# SDRAM.net
KiCad netlist of a schematic drawn in Altium Designer
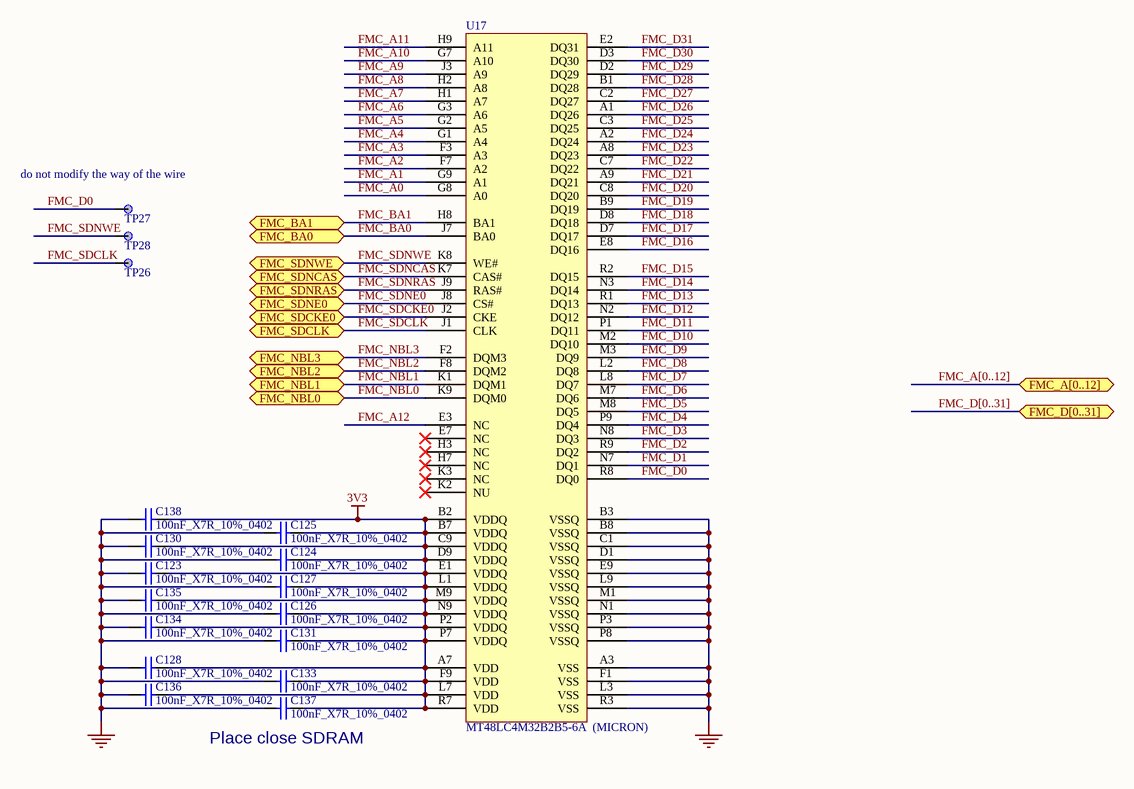
[diagram p0: SDRAM.SchDoc]

(export (version "E")
  (design (tool "Eeschema 10.0.6"))
  (components
    (comp (ref "C123")
      (value "100nF_X7R_10%_0402")
      (footprint "0402C")
      (description "Capacitor,100nF,16V,X7R,10%,0402,YAGEO")
      (libsource (lib "MCD_TOOLS") (part "Cap_100nF_X7R_10%_0402"))
    )
    (comp (ref "C124")
      (value "100nF_X7R_10%_0402")
      (footprint "0402C")
      (description "Capacitor,100nF,16V,X7R,10%,0402,YAGEO")
      (libsource (lib "MCD_TOOLS") (part "Cap_100nF_X7R_10%_0402"))
    )
    (comp (ref "C125")
      (value "100nF_X7R_10%_0402")
      (footprint "0402C")
      (description "Capacitor,100nF,16V,X7R,10%,0402,YAGEO")
      (libsource (lib "MCD_TOOLS") (part "Cap_100nF_X7R_10%_0402"))
    )
    (comp (ref "C126")
      (value "100nF_X7R_10%_0402")
      (footprint "0402C")
      (description "Capacitor,100nF,16V,X7R,10%,0402,YAGEO")
      (libsource (lib "MCD_TOOLS") (part "Cap_100nF_X7R_10%_0402"))
    )
    (comp (ref "C127")
      (value "100nF_X7R_10%_0402")
      (footprint "0402C")
      (description "Capacitor,100nF,16V,X7R,10%,0402,YAGEO")
      (libsource (lib "MCD_TOOLS") (part "Cap_100nF_X7R_10%_0402"))
    )
    (comp (ref "C128")
      (value "100nF_X7R_10%_0402")
      (footprint "0402C")
      (description "Capacitor,100nF,16V,X7R,10%,0402,YAGEO")
      (libsource (lib "MCD_TOOLS") (part "Cap_100nF_X7R_10%_0402"))
    )
    (comp (ref "C130")
      (value "100nF_X7R_10%_0402")
      (footprint "0402C")
      (description "Capacitor,100nF,16V,X7R,10%,0402,YAGEO")
      (libsource (lib "MCD_TOOLS") (part "Cap_100nF_X7R_10%_0402"))
    )
    (comp (ref "C131")
      (value "100nF_X7R_10%_0402")
      (footprint "0402C")
      (description "Capacitor,100nF,16V,X7R,10%,0402,YAGEO")
      (libsource (lib "MCD_TOOLS") (part "Cap_100nF_X7R_10%_0402"))
    )
    (comp (ref "C133")
      (value "100nF_X7R_10%_0402")
      (footprint "0402C")
      (description "Capacitor,100nF,16V,X7R,10%,0402,YAGEO")
      (libsource (lib "MCD_TOOLS") (part "Cap_100nF_X7R_10%_0402"))
    )
    (comp (ref "C134")
      (value "100nF_X7R_10%_0402")
      (footprint "0402C")
      (description "Capacitor,100nF,16V,X7R,10%,0402,YAGEO")
      (libsource (lib "MCD_TOOLS") (part "Cap_100nF_X7R_10%_0402"))
    )
    (comp (ref "C135")
      (value "100nF_X7R_10%_0402")
      (footprint "0402C")
      (description "Capacitor,100nF,16V,X7R,10%,0402,YAGEO")
      (libsource (lib "MCD_TOOLS") (part "Cap_100nF_X7R_10%_0402"))
    )
    (comp (ref "C136")
      (value "100nF_X7R_10%_0402")
      (footprint "0402C")
      (description "Capacitor,100nF,16V,X7R,10%,0402,YAGEO")
      (libsource (lib "MCD_TOOLS") (part "Cap_100nF_X7R_10%_0402"))
    )
    (comp (ref "C137")
      (value "100nF_X7R_10%_0402")
      (footprint "0402C")
      (description "Capacitor,100nF,16V,X7R,10%,0402,YAGEO")
      (libsource (lib "MCD_TOOLS") (part "Cap_100nF_X7R_10%_0402"))
    )
    (comp (ref "C138")
      (value "100nF_X7R_10%_0402")
      (footprint "0402C")
      (description "Capacitor,100nF,16V,X7R,10%,0402,YAGEO")
      (libsource (lib "MCD_TOOLS") (part "Cap_100nF_X7R_10%_0402"))
    )
    (comp (ref "TP26")
      (value "TP")
      (footprint "TP_C40")
      (description "Test Point CMS")
      (libsource (lib "MCD_TOOLS_CONNECTOR") (part "TP"))
    )
    (comp (ref "TP27")
      (value "TP")
      (footprint "TP_C40")
      (description "Test Point CMS")
      (libsource (lib "MCD_TOOLS_CONNECTOR") (part "TP"))
    )
    (comp (ref "TP28")
      (value "TP")
      (footprint "TP_C40")
      (description "Test Point CMS")
      (libsource (lib "MCD_TOOLS_CONNECTOR") (part "TP"))
    )
    (comp (ref "U17")
      (value "MT48LC4M32B2B5-6A  (MICRON)")
      (footprint "FBGA90_0R8_8X13")
      (description "SDRAM 128MBIT (4M x 32) 166MHZ 90-VFBGA (8x13)")
      (libsource (lib "MCD_TOOLS") (part "MT48LC4M32B2B5-6A"))
    )
  )
  (nets
    (net (code "1") (name "/FMC_A0") (class "Default")
      (node (ref "U17") (pin "G8") (pinfunction "A0_G8") (pintype "passive"))
    )
    (net (code "2") (name "/FMC_A1") (class "Default")
      (node (ref "U17") (pin "G9") (pinfunction "A1_G9") (pintype "passive"))
    )
    (net (code "3") (name "/FMC_A2") (class "Default")
      (node (ref "U17") (pin "F7") (pinfunction "A2_F7") (pintype "passive"))
    )
    (net (code "4") (name "/FMC_A3") (class "Default")
      (node (ref "U17") (pin "F3") (pinfunction "A3_F3") (pintype "passive"))
    )
    (net (code "5") (name "/FMC_A4") (class "Default")
      (node (ref "U17") (pin "G1") (pinfunction "A4_G1") (pintype "passive"))
    )
    (net (code "6") (name "/FMC_A5") (class "Default")
      (node (ref "U17") (pin "G2") (pinfunction "A5_G2") (pintype "passive"))
    )
    (net (code "7") (name "/FMC_A6") (class "Default")
      (node (ref "U17") (pin "G3") (pinfunction "A6_G3") (pintype "passive"))
    )
    (net (code "8") (name "/FMC_A7") (class "Default")
      (node (ref "U17") (pin "H1") (pinfunction "A7_H1") (pintype "passive"))
    )
    (net (code "9") (name "/FMC_A8") (class "Default")
      (node (ref "U17") (pin "H2") (pinfunction "A8_H2") (pintype "passive"))
    )
    (net (code "10") (name "/FMC_A9") (class "Default")
      (node (ref "U17") (pin "J3") (pinfunction "A9_J3") (pintype "passive"))
    )
    (net (code "11") (name "/FMC_A10") (class "Default")
      (node (ref "U17") (pin "G7") (pinfunction "A10_G7") (pintype "passive"))
    )
    (net (code "12") (name "/FMC_A11") (class "Default")
      (node (ref "U17") (pin "H9") (pinfunction "A11_H9") (pintype "passive"))
    )
    (net (code "13") (name "/FMC_A12") (class "Default")
      (node (ref "U17") (pin "E3") (pinfunction "NC_E3") (pintype "passive"))
    )
    (net (code "15") (name "/FMC_BA0") (class "Default")
      (node (ref "U17") (pin "J7") (pinfunction "BA0_J7") (pintype "passive"))
    )
    (net (code "16") (name "/FMC_BA1") (class "Default")
      (node (ref "U17") (pin "H8") (pinfunction "BA1_H8") (pintype "passive"))
    )
    (net (code "17") (name "/FMC_D0") (class "Default")
      (node (ref "TP27") (pin "1") (pinfunction "1_1") (pintype "passive"))
      (node (ref "U17") (pin "R8") (pinfunction "DQ0_R8") (pintype "passive"))
    )
    (net (code "18") (name "/FMC_D1") (class "Default")
      (node (ref "U17") (pin "N7") (pinfunction "DQ1_N7") (pintype "passive"))
    )
    (net (code "19") (name "/FMC_D2") (class "Default")
      (node (ref "U17") (pin "R9") (pinfunction "DQ2_R9") (pintype "passive"))
    )
    (net (code "20") (name "/FMC_D3") (class "Default")
      (node (ref "U17") (pin "N8") (pinfunction "DQ3_N8") (pintype "passive"))
    )
    (net (code "21") (name "/FMC_D4") (class "Default")
      (node (ref "U17") (pin "P9") (pinfunction "DQ4_P9") (pintype "passive"))
    )
    (net (code "22") (name "/FMC_D5") (class "Default")
      (node (ref "U17") (pin "M8") (pinfunction "DQ5_M8") (pintype "passive"))
    )
    (net (code "23") (name "/FMC_D6") (class "Default")
      (node (ref "U17") (pin "M7") (pinfunction "DQ6_M7") (pintype "passive"))
    )
    (net (code "24") (name "/FMC_D7") (class "Default")
      (node (ref "U17") (pin "L8") (pinfunction "DQ7_L8") (pintype "passive"))
    )
    (net (code "25") (name "/FMC_D8") (class "Default")
      (node (ref "U17") (pin "L2") (pinfunction "DQ8_L2") (pintype "passive"))
    )
    (net (code "26") (name "/FMC_D9") (class "Default")
      (node (ref "U17") (pin "M3") (pinfunction "DQ9_M3") (pintype "passive"))
    )
    (net (code "27") (name "/FMC_D10") (class "Default")
      (node (ref "U17") (pin "M2") (pinfunction "DQ10_M2") (pintype "passive"))
    )
    (net (code "28") (name "/FMC_D11") (class "Default")
      (node (ref "U17") (pin "P1") (pinfunction "DQ11_P1") (pintype "passive"))
    )
    (net (code "29") (name "/FMC_D12") (class "Default")
      (node (ref "U17") (pin "N2") (pinfunction "DQ12_N2") (pintype "passive"))
    )
    (net (code "30") (name "/FMC_D13") (class "Default")
      (node (ref "U17") (pin "R1") (pinfunction "DQ13_R1") (pintype "passive"))
    )
    (net (code "31") (name "/FMC_D14") (class "Default")
      (node (ref "U17") (pin "N3") (pinfunction "DQ14_N3") (pintype "passive"))
    )
    (net (code "32") (name "/FMC_D15") (class "Default")
      (node (ref "U17") (pin "R2") (pinfunction "DQ15_R2") (pintype "passive"))
    )
    (net (code "33") (name "/FMC_D16") (class "Default")
      (node (ref "U17") (pin "E8") (pinfunction "DQ16_E8") (pintype "passive"))
    )
    (net (code "34") (name "/FMC_D17") (class "Default")
      (node (ref "U17") (pin "D7") (pinfunction "DQ17_D7") (pintype "passive"))
    )
    (net (code "35") (name "/FMC_D18") (class "Default")
      (node (ref "U17") (pin "D8") (pinfunction "DQ18_D8") (pintype "passive"))
    )
    (net (code "36") (name "/FMC_D19") (class "Default")
      (node (ref "U17") (pin "B9") (pinfunction "DQ19_B9") (pintype "passive"))
    )
    (net (code "37") (name "/FMC_D20") (class "Default")
      (node (ref "U17") (pin "C8") (pinfunction "DQ20_C8") (pintype "passive"))
    )
    (net (code "38") (name "/FMC_D21") (class "Default")
      (node (ref "U17") (pin "A9") (pinfunction "DQ21_A9") (pintype "passive"))
    )
    (net (code "39") (name "/FMC_D22") (class "Default")
      (node (ref "U17") (pin "C7") (pinfunction "DQ22_C7") (pintype "passive"))
    )
    (net (code "40") (name "/FMC_D23") (class "Default")
      (node (ref "U17") (pin "A8") (pinfunction "DQ23_A8") (pintype "passive"))
    )
    (net (code "41") (name "/FMC_D24") (class "Default")
      (node (ref "U17") (pin "A2") (pinfunction "DQ24_A2") (pintype "passive"))
    )
    (net (code "42") (name "/FMC_D25") (class "Default")
      (node (ref "U17") (pin "C3") (pinfunction "DQ25_C3") (pintype "passive"))
    )
    (net (code "43") (name "/FMC_D26") (class "Default")
      (node (ref "U17") (pin "A1") (pinfunction "DQ26_A1") (pintype "passive"))
    )
    (net (code "44") (name "/FMC_D27") (class "Default")
      (node (ref "U17") (pin "C2") (pinfunction "DQ27_C2") (pintype "passive"))
    )
    (net (code "45") (name "/FMC_D28") (class "Default")
      (node (ref "U17") (pin "B1") (pinfunction "DQ28_B1") (pintype "passive"))
    )
    (net (code "46") (name "/FMC_D29") (class "Default")
      (node (ref "U17") (pin "D2") (pinfunction "DQ29_D2") (pintype "passive"))
    )
    (net (code "47") (name "/FMC_D30") (class "Default")
      (node (ref "U17") (pin "D3") (pinfunction "DQ30_D3") (pintype "passive"))
    )
    (net (code "48") (name "/FMC_D31") (class "Default")
      (node (ref "U17") (pin "E2") (pinfunction "DQ31_E2") (pintype "passive"))
    )
    (net (code "50") (name "/FMC_NBL0") (class "Default")
      (node (ref "U17") (pin "K9") (pinfunction "DQM0_K9") (pintype "passive"))
    )
    (net (code "51") (name "/FMC_NBL1") (class "Default")
      (node (ref "U17") (pin "K1") (pinfunction "DQM1_K1") (pintype "passive"))
    )
    (net (code "52") (name "/FMC_NBL2") (class "Default")
      (node (ref "U17") (pin "F8") (pinfunction "DQM2_F8") (pintype "passive"))
    )
    (net (code "53") (name "/FMC_NBL3") (class "Default")
      (node (ref "U17") (pin "F2") (pinfunction "DQM3_F2") (pintype "passive"))
    )
    (net (code "54") (name "/FMC_SDCKE0") (class "Default")
      (node (ref "U17") (pin "J2") (pinfunction "CKE_J2") (pintype "passive"))
    )
    (net (code "55") (name "/FMC_SDCLK") (class "Default")
      (node (ref "TP26") (pin "1") (pinfunction "1_1") (pintype "passive"))
      (node (ref "U17") (pin "J1") (pinfunction "CLK_J1") (pintype "passive"))
    )
    (net (code "56") (name "/FMC_SDNCAS") (class "Default")
      (node (ref "U17") (pin "K7") (pinfunction "CAS#_K7") (pintype "passive"))
    )
    (net (code "57") (name "/FMC_SDNE0") (class "Default")
      (node (ref "U17") (pin "J8") (pinfunction "CS#_J8") (pintype "passive"))
    )
    (net (code "58") (name "/FMC_SDNRAS") (class "Default")
      (node (ref "U17") (pin "J9") (pinfunction "RAS#_J9") (pintype "passive"))
    )
    (net (code "59") (name "/FMC_SDNWE") (class "Default")
      (node (ref "TP28") (pin "1") (pinfunction "1_1") (pintype "passive"))
      (node (ref "U17") (pin "K8") (pinfunction "WE#_K8") (pintype "passive"))
    )
    (net (code "60") (name "3V3") (class "Default")
      (node (ref "C123") (pin "2") (pinfunction "2_2") (pintype "passive"))
      (node (ref "C124") (pin "2") (pinfunction "2_2") (pintype "passive"))
      (node (ref "C125") (pin "2") (pinfunction "2_2") (pintype "passive"))
      (node (ref "C126") (pin "2") (pinfunction "2_2") (pintype "passive"))
      (node (ref "C127") (pin "2") (pinfunction "2_2") (pintype "passive"))
      (node (ref "C128") (pin "2") (pinfunction "2_2") (pintype "passive"))
      (node (ref "C130") (pin "2") (pinfunction "2_2") (pintype "passive"))
      (node (ref "C131") (pin "2") (pinfunction "2_2") (pintype "passive"))
      (node (ref "C133") (pin "2") (pinfunction "2_2") (pintype "passive"))
      (node (ref "C134") (pin "2") (pinfunction "2_2") (pintype "passive"))
      (node (ref "C135") (pin "2") (pinfunction "2_2") (pintype "passive"))
      (node (ref "C136") (pin "2") (pinfunction "2_2") (pintype "passive"))
      (node (ref "C137") (pin "2") (pinfunction "2_2") (pintype "passive"))
      (node (ref "C138") (pin "2") (pinfunction "2_2") (pintype "passive"))
      (node (ref "U17") (pin "A7") (pinfunction "VDD_A7") (pintype "passive"))
      (node (ref "U17") (pin "B2") (pinfunction "VDDQ_B2") (pintype "passive"))
      (node (ref "U17") (pin "B7") (pinfunction "VDDQ_B7") (pintype "passive"))
      (node (ref "U17") (pin "C9") (pinfunction "VDDQ_C9") (pintype "passive"))
      (node (ref "U17") (pin "D9") (pinfunction "VDDQ_D9") (pintype "passive"))
      (node (ref "U17") (pin "E1") (pinfunction "VDDQ_E1") (pintype "passive"))
      (node (ref "U17") (pin "F9") (pinfunction "VDD_F9") (pintype "passive"))
      (node (ref "U17") (pin "L1") (pinfunction "VDDQ_L1") (pintype "passive"))
      (node (ref "U17") (pin "L7") (pinfunction "VDD_L7") (pintype "passive"))
      (node (ref "U17") (pin "M9") (pinfunction "VDDQ_M9") (pintype "passive"))
      (node (ref "U17") (pin "N9") (pinfunction "VDDQ_N9") (pintype "passive"))
      (node (ref "U17") (pin "P2") (pinfunction "VDDQ_P2") (pintype "passive"))
      (node (ref "U17") (pin "P7") (pinfunction "VDDQ_P7") (pintype "passive"))
      (node (ref "U17") (pin "R7") (pinfunction "VDD_R7") (pintype "passive"))
    )
    (net (code "61") (name "GND") (class "Default")
      (node (ref "C123") (pin "1") (pinfunction "1_1") (pintype "passive"))
      (node (ref "C124") (pin "1") (pinfunction "1_1") (pintype "passive"))
      (node (ref "C125") (pin "1") (pinfunction "1_1") (pintype "passive"))
      (node (ref "C126") (pin "1") (pinfunction "1_1") (pintype "passive"))
      (node (ref "C127") (pin "1") (pinfunction "1_1") (pintype "passive"))
      (node (ref "C128") (pin "1") (pinfunction "1_1") (pintype "passive"))
      (node (ref "C130") (pin "1") (pinfunction "1_1") (pintype "passive"))
      (node (ref "C131") (pin "1") (pinfunction "1_1") (pintype "passive"))
      (node (ref "C133") (pin "1") (pinfunction "1_1") (pintype "passive"))
      (node (ref "C134") (pin "1") (pinfunction "1_1") (pintype "passive"))
      (node (ref "C135") (pin "1") (pinfunction "1_1") (pintype "passive"))
      (node (ref "C136") (pin "1") (pinfunction "1_1") (pintype "passive"))
      (node (ref "C137") (pin "1") (pinfunction "1_1") (pintype "passive"))
      (node (ref "C138") (pin "1") (pinfunction "1_1") (pintype "passive"))
      (node (ref "U17") (pin "A3") (pinfunction "VSS_A3") (pintype "passive"))
      (node (ref "U17") (pin "B3") (pinfunction "VSSQ_B3") (pintype "passive"))
      (node (ref "U17") (pin "B8") (pinfunction "VSSQ_B8") (pintype "passive"))
      (node (ref "U17") (pin "C1") (pinfunction "VSSQ_C1") (pintype "passive"))
      (node (ref "U17") (pin "D1") (pinfunction "VSSQ_D1") (pintype "passive"))
      (node (ref "U17") (pin "E9") (pinfunction "VSSQ_E9") (pintype "passive"))
      (node (ref "U17") (pin "F1") (pinfunction "VSS_F1") (pintype "passive"))
      (node (ref "U17") (pin "L3") (pinfunction "VSS_L3") (pintype "passive"))
      (node (ref "U17") (pin "L9") (pinfunction "VSSQ_L9") (pintype "passive"))
      (node (ref "U17") (pin "M1") (pinfunction "VSSQ_M1") (pintype "passive"))
      (node (ref "U17") (pin "N1") (pinfunction "VSSQ_N1") (pintype "passive"))
      (node (ref "U17") (pin "P3") (pinfunction "VSSQ_P3") (pintype "passive"))
      (node (ref "U17") (pin "P8") (pinfunction "VSSQ_P8") (pintype "passive"))
      (node (ref "U17") (pin "R3") (pinfunction "VSS_R3") (pintype "passive"))
    )
    (net (code "62") (name "unconnected-(U17-NC-PadE7)") (class "Default")
      (node (ref "U17") (pin "E7") (pinfunction "NC_E7") (pintype "passive+no_connect"))
    )
    (net (code "63") (name "unconnected-(U17-NC-PadH3)") (class "Default")
      (node (ref "U17") (pin "H3") (pinfunction "NC_H3") (pintype "passive+no_connect"))
    )
    (net (code "64") (name "unconnected-(U17-NC-PadH7)") (class "Default")
      (node (ref "U17") (pin "H7") (pinfunction "NC_H7") (pintype "passive+no_connect"))
    )
    (net (code "65") (name "unconnected-(U17-NC-PadK3)") (class "Default")
      (node (ref "U17") (pin "K3") (pinfunction "NC_K3") (pintype "passive+no_connect"))
    )
    (net (code "66") (name "unconnected-(U17-NU-PadK2)") (class "Default")
      (node (ref "U17") (pin "K2") (pinfunction "NU_K2") (pintype "passive+no_connect"))
    )
  )
)
